# main.net
KiCad netlist of a schematic drawn in EAGLE
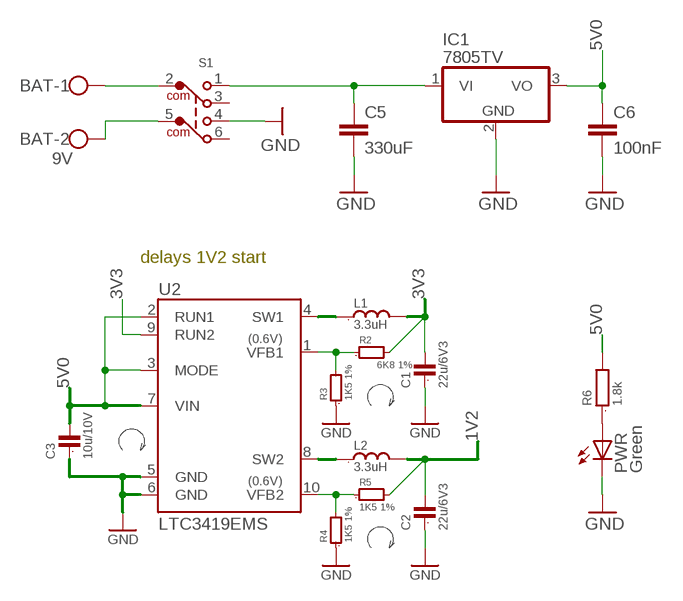
[diagram p0: schematic, sheet 1]
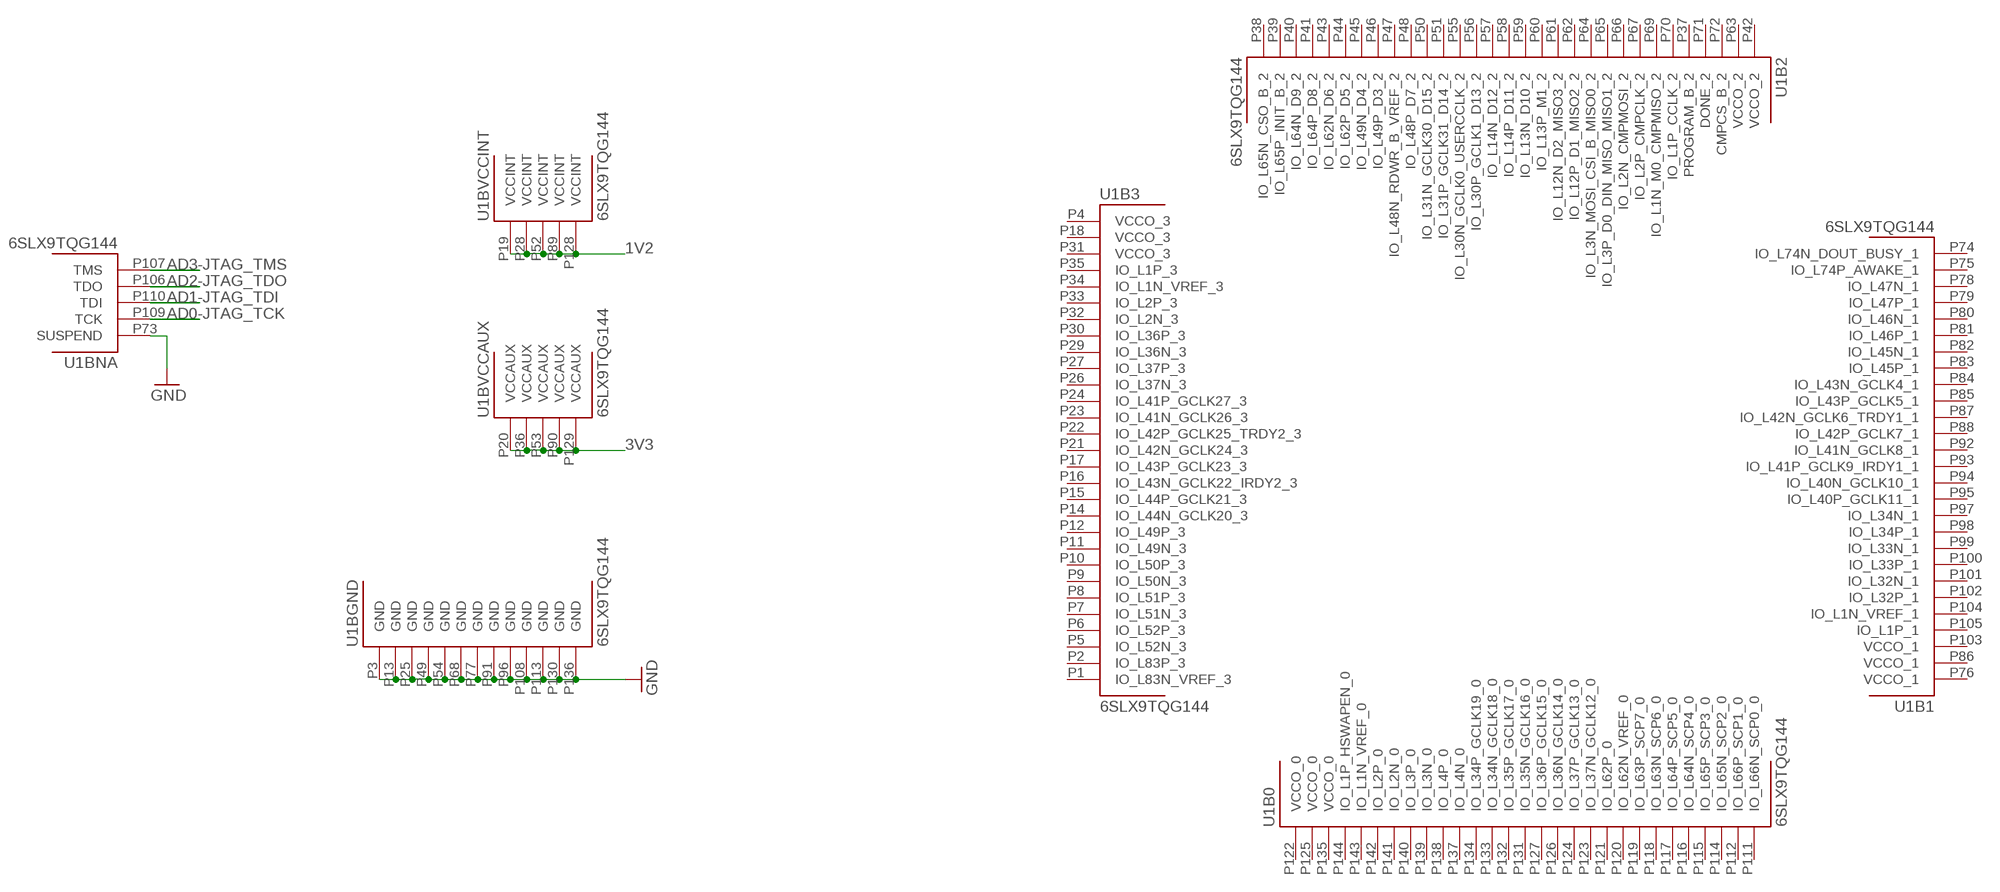
[diagram p1: schematic, sheet 2]

(export (version "E")
  (design (tool "Eeschema 10.0.6"))
  (components
    (comp (ref "BAT")
      (value "9V")
      (footprint "eagle-import:W237-102")
      (fields (field (name "MPN") "237-102"))
      (libsource (lib "eagle-import") (part "W237-102"))
    )
    (comp (ref "C1")
      (value "22u/6V3")
      (footprint "eagle-import:0805")
      (fields (field (name "PARTNO") "GRM21BR60J226ME39L"))
      (libsource (lib "eagle-import") (part "C0805"))
    )
    (comp (ref "C2")
      (value "22u/6V3")
      (footprint "eagle-import:0805")
      (fields (field (name "PARTNO") "GRM21BR60J226ME39L"))
      (libsource (lib "eagle-import") (part "C0805"))
    )
    (comp (ref "C3")
      (value "10u/10V")
      (footprint "eagle-import:0805")
      (fields (field (name "PARTNO") "C0805C106K9PACTU"))
      (libsource (lib "eagle-import") (part "C0805"))
    )
    (comp (ref "C5")
      (value "330uF")
      (footprint "eagle-import:C0805")
      (libsource (lib "eagle-import") (part "C-EUC0805"))
    )
    (comp (ref "C6")
      (value "100nF")
      (footprint "eagle-import:C0805")
      (libsource (lib "eagle-import") (part "C-EUC0805"))
    )
    (comp (ref "IC1")
      (value "7805TV")
      (footprint "eagle-import:TO220V")
      (libsource (lib "eagle-import") (part "78TV05"))
    )
    (comp (ref "L1")
      (value "3.3uH")
      (footprint "eagle-import:VLS3015")
      (fields (field (name "PARTNO") "VLS3015T-3R3M1R2"))
      (libsource (lib "eagle-import") (part "L_VLS3015"))
    )
    (comp (ref "L2")
      (value "3.3uH")
      (footprint "eagle-import:VLS3015")
      (fields (field (name "PARTNO") "VLS3015T-3R3M1R2"))
      (libsource (lib "eagle-import") (part "L_VLS3015"))
    )
    (comp (ref "PWR")
      (value "Green")
      (footprint "eagle-import:CHIP-LED0805")
      (fields (field (name "PARTNO") "LTST-C171EKT"))
      (libsource (lib "eagle-import") (part "LEDCHIP-LED0805"))
    )
    (comp (ref "R2")
      (value "6K8 1%")
      (footprint "eagle-import:0603")
      (fields (field (name "PARTNO") "CRCW06036K80FKEA"))
      (libsource (lib "eagle-import") (part "R-SMALL0603"))
    )
    (comp (ref "R3")
      (value "1K5 1%")
      (footprint "eagle-import:0603")
      (fields (field (name "PARTNO") "CRCW06031K50FKEA"))
      (libsource (lib "eagle-import") (part "R-SMALL0603"))
    )
    (comp (ref "R4")
      (value "1K5 1%")
      (footprint "eagle-import:0603")
      (fields (field (name "PARTNO") "CRCW06031K50FKEA"))
      (libsource (lib "eagle-import") (part "R-SMALL0603"))
    )
    (comp (ref "R5")
      (value "1K5 1%")
      (footprint "eagle-import:0603")
      (fields (field (name "PARTNO") "CRCW06031K50FKEA"))
      (libsource (lib "eagle-import") (part "R-SMALL0603"))
    )
    (comp (ref "R6")
      (value "1.8k")
      (footprint "eagle-import:0603")
      (fields (field (name "PARTNO") "RMCF0603JT1K80"))
      (libsource (lib "eagle-import") (part "R0603"))
    )
    (comp (ref "S1")
      (value "452404020202")
      (footprint "eagle-import:452404020202")
      (libsource (lib "eagle-import") (part "452404020202"))
    )
    (comp (ref "U2")
      (value "LTC3419EMS")
      (footprint "eagle-import:MSOP10")
      (fields (field (name "PARTNO") "LTC3419EMS#PBF"))
      (libsource (lib "eagle-import") (part "LTC3419MSE"))
    )
    (comp (ref "U1")
      (value "6SLX9TQG144")
      (footprint "eagle-import:TQ144")
      (libsource (lib "eagle-import") (part "6SLX9TQG144"))
    )
  )
  (nets
    (net (code "1") (name "1V2") (class "Default")
      (node (ref "C2") (pin "2") (pinfunction "2_2") (pintype "passive"))
      (node (ref "L2") (pin "2") (pinfunction "2_2") (pintype "passive"))
      (node (ref "R5") (pin "2") (pinfunction "2_2") (pintype "passive"))
      (node (ref "U1") (pin "P128") (pinfunction "VCCINT_P128") (pintype "input"))
      (node (ref "U1") (pin "P19") (pinfunction "VCCINT_P19") (pintype "input"))
      (node (ref "U1") (pin "P28") (pinfunction "VCCINT_P28") (pintype "input"))
      (node (ref "U1") (pin "P52") (pinfunction "VCCINT_P52") (pintype "input"))
      (node (ref "U1") (pin "P89") (pinfunction "VCCINT_P89") (pintype "input"))
    )
    (net (code "2") (name "3V3") (class "Default")
      (node (ref "C1") (pin "2") (pinfunction "2_2") (pintype "passive"))
      (node (ref "L1") (pin "2") (pinfunction "2_2") (pintype "passive"))
      (node (ref "R2") (pin "2") (pinfunction "2_2") (pintype "passive"))
      (node (ref "U1") (pin "P129") (pinfunction "VCCAUX_P129") (pintype "input"))
      (node (ref "U1") (pin "P20") (pinfunction "VCCAUX_P20") (pintype "input"))
      (node (ref "U1") (pin "P36") (pinfunction "VCCAUX_P36") (pintype "input"))
      (node (ref "U1") (pin "P53") (pinfunction "VCCAUX_P53") (pintype "input"))
      (node (ref "U1") (pin "P90") (pinfunction "VCCAUX_P90") (pintype "input"))
      (node (ref "U2") (pin "9") (pinfunction "RUN2_9") (pintype "input"))
    )
    (net (code "3") (name "5V0") (class "Default")
      (node (ref "C3") (pin "2") (pinfunction "2_2") (pintype "passive"))
      (node (ref "C6") (pin "1") (pinfunction "1_1") (pintype "passive"))
      (node (ref "IC1") (pin "3") (pinfunction "VO_3") (pintype "passive"))
      (node (ref "R6") (pin "2") (pinfunction "2_2") (pintype "passive"))
      (node (ref "U2") (pin "2") (pinfunction "RUN1_2") (pintype "input"))
      (node (ref "U2") (pin "3") (pinfunction "MODE_3") (pintype "input"))
      (node (ref "U2") (pin "7") (pinfunction "VIN_7") (pintype "input"))
    )
    (net (code "4") (name "AD0-JTAG_TCK") (class "Default")
      (node (ref "U1") (pin "P109") (pinfunction "TCK_P109") (pintype "input"))
    )
    (net (code "5") (name "AD1-JTAG_TDI") (class "Default")
      (node (ref "U1") (pin "P110") (pinfunction "TDI_P110") (pintype "input"))
    )
    (net (code "6") (name "AD2-JTAG_TDO") (class "Default")
      (node (ref "U1") (pin "P106") (pinfunction "TDO_P106") (pintype "output"))
    )
    (net (code "7") (name "AD3-JTAG_TMS") (class "Default")
      (node (ref "U1") (pin "P107") (pinfunction "TMS_P107") (pintype "input"))
    )
    (net (code "8") (name "GND") (class "Default")
      (node (ref "C1") (pin "1") (pinfunction "1_1") (pintype "passive"))
      (node (ref "C2") (pin "1") (pinfunction "1_1") (pintype "passive"))
      (node (ref "C3") (pin "1") (pinfunction "1_1") (pintype "passive"))
      (node (ref "C5") (pin "2") (pinfunction "2_2") (pintype "passive"))
      (node (ref "C6") (pin "2") (pinfunction "2_2") (pintype "passive"))
      (node (ref "IC1") (pin "2") (pinfunction "GND_2") (pintype "passive"))
      (node (ref "PWR") (pin "C") (pinfunction "C_C") (pintype "passive"))
      (node (ref "R3") (pin "1") (pinfunction "1_1") (pintype "passive"))
      (node (ref "R4") (pin "1") (pinfunction "1_1") (pintype "passive"))
      (node (ref "S1") (pin "4") (pinfunction "4_4") (pintype "passive"))
      (node (ref "U1") (pin "P108") (pinfunction "GND_P108") (pintype "power_in"))
      (node (ref "U1") (pin "P113") (pinfunction "GND_P113") (pintype "power_in"))
      (node (ref "U1") (pin "P13") (pinfunction "GND_P13") (pintype "power_in"))
      (node (ref "U1") (pin "P130") (pinfunction "GND_P130") (pintype "power_in"))
      (node (ref "U1") (pin "P136") (pinfunction "GND_P136") (pintype "power_in"))
      (node (ref "U1") (pin "P25") (pinfunction "GND_P25") (pintype "power_in"))
      (node (ref "U1") (pin "P3") (pinfunction "GND_P3") (pintype "power_in"))
      (node (ref "U1") (pin "P49") (pinfunction "GND_P49") (pintype "power_in"))
      (node (ref "U1") (pin "P54") (pinfunction "GND_P54") (pintype "power_in"))
      (node (ref "U1") (pin "P68") (pinfunction "GND_P68") (pintype "power_in"))
      (node (ref "U1") (pin "P73") (pinfunction "SUSPEND_P73") (pintype "input"))
      (node (ref "U1") (pin "P77") (pinfunction "GND_P77") (pintype "power_in"))
      (node (ref "U1") (pin "P91") (pinfunction "GND_P91") (pintype "power_in"))
      (node (ref "U1") (pin "P96") (pinfunction "GND_P96") (pintype "power_in"))
      (node (ref "U2") (pin "5") (pinfunction "GND_5") (pintype "power_in"))
      (node (ref "U2") (pin "6") (pinfunction "GND_6") (pintype "power_in"))
    )
    (net (code "9") (name "Net-(BATA-KL)") (class "Default")
      (node (ref "BAT") (pin "1") (pinfunction "KL_1") (pintype "passive"))
      (node (ref "S1") (pin "2") (pinfunction "COM_2") (pintype "passive"))
    )
    (net (code "10") (name "Net-(BATB-KL)") (class "Default")
      (node (ref "BAT") (pin "2") (pinfunction "KL_2") (pintype "passive"))
      (node (ref "S1") (pin "5") (pinfunction "COM1_5") (pintype "passive"))
    )
    (net (code "11") (name "Net-(IC1-VI)") (class "Default")
      (node (ref "C5") (pin "1") (pinfunction "1_1") (pintype "passive"))
      (node (ref "IC1") (pin "1") (pinfunction "VI_1") (pintype "input"))
      (node (ref "S1") (pin "1") (pinfunction "1_1") (pintype "passive"))
    )
    (net (code "12") (name "Net-(PWR-PadA)") (class "Default")
      (node (ref "PWR") (pin "A") (pinfunction "A_A") (pintype "passive"))
      (node (ref "R6") (pin "1") (pinfunction "1_1") (pintype "passive"))
    )
    (net (code "13") (name "Net-(U2-SW1)") (class "Default")
      (node (ref "L1") (pin "1") (pinfunction "1_1") (pintype "passive"))
      (node (ref "U2") (pin "4") (pinfunction "SW1_4") (pintype "output"))
    )
    (net (code "14") (name "Net-(U2-SW2)") (class "Default")
      (node (ref "L2") (pin "1") (pinfunction "1_1") (pintype "passive"))
      (node (ref "U2") (pin "8") (pinfunction "SW2_8") (pintype "output"))
    )
    (net (code "15") (name "Net-(U2-VFB1)") (class "Default")
      (node (ref "R2") (pin "1") (pinfunction "1_1") (pintype "passive"))
      (node (ref "R3") (pin "2") (pinfunction "2_2") (pintype "passive"))
      (node (ref "U2") (pin "1") (pinfunction "VFB1_1") (pintype "input"))
    )
    (net (code "16") (name "Net-(U2-VFB2)") (class "Default")
      (node (ref "R4") (pin "2") (pinfunction "2_2") (pintype "passive"))
      (node (ref "R5") (pin "1") (pinfunction "1_1") (pintype "passive"))
      (node (ref "U2") (pin "10") (pinfunction "VFB2_10") (pintype "input"))
    )
    (net (code "17") (name "unconnected-(S1-Pad3)") (class "Default")
      (node (ref "S1") (pin "3") (pinfunction "3_3") (pintype "passive"))
    )
    (net (code "18") (name "unconnected-(S1-Pad6)") (class "Default")
      (node (ref "S1") (pin "6") (pinfunction "6_6") (pintype "passive"))
    )
    (net (code "19") (name "unconnected-(U1A-IO_L1N_VREF_0-PadP143)") (class "Default")
      (node (ref "U1") (pin "P143") (pinfunction "IO_L1N_VREF_0_P143") (pintype "bidirectional"))
    )
    (net (code "20") (name "unconnected-(U1A-IO_L1P_HSWAPEN_0-PadP144)") (class "Default")
      (node (ref "U1") (pin "P144") (pinfunction "IO_L1P_HSWAPEN_0_P144") (pintype "bidirectional"))
    )
    (net (code "21") (name "unconnected-(U1A-IO_L2N_0-PadP141)") (class "Default")
      (node (ref "U1") (pin "P141") (pinfunction "IO_L2N_0_P141") (pintype "bidirectional"))
    )
    (net (code "22") (name "unconnected-(U1A-IO_L2P_0-PadP142)") (class "Default")
      (node (ref "U1") (pin "P142") (pinfunction "IO_L2P_0_P142") (pintype "bidirectional"))
    )
    (net (code "23") (name "unconnected-(U1A-IO_L3N_0-PadP139)") (class "Default")
      (node (ref "U1") (pin "P139") (pinfunction "IO_L3N_0_P139") (pintype "bidirectional"))
    )
    (net (code "24") (name "unconnected-(U1A-IO_L3P_0-PadP140)") (class "Default")
      (node (ref "U1") (pin "P140") (pinfunction "IO_L3P_0_P140") (pintype "bidirectional"))
    )
    (net (code "25") (name "unconnected-(U1A-IO_L4N_0-PadP137)") (class "Default")
      (node (ref "U1") (pin "P137") (pinfunction "IO_L4N_0_P137") (pintype "bidirectional"))
    )
    (net (code "26") (name "unconnected-(U1A-IO_L4P_0-PadP138)") (class "Default")
      (node (ref "U1") (pin "P138") (pinfunction "IO_L4P_0_P138") (pintype "bidirectional"))
    )
    (net (code "27") (name "unconnected-(U1A-IO_L34N_GCLK18_0-PadP133)") (class "Default")
      (node (ref "U1") (pin "P133") (pinfunction "IO_L34N_GCLK18_0_P133") (pintype "bidirectional"))
    )
    (net (code "28") (name "unconnected-(U1A-IO_L34P_GCLK19_0-PadP134)") (class "Default")
      (node (ref "U1") (pin "P134") (pinfunction "IO_L34P_GCLK19_0_P134") (pintype "bidirectional"))
    )
    (net (code "29") (name "unconnected-(U1A-IO_L35N_GCLK16_0-PadP131)") (class "Default")
      (node (ref "U1") (pin "P131") (pinfunction "IO_L35N_GCLK16_0_P131") (pintype "bidirectional"))
    )
    (net (code "30") (name "unconnected-(U1A-IO_L35P_GCLK17_0-PadP132)") (class "Default")
      (node (ref "U1") (pin "P132") (pinfunction "IO_L35P_GCLK17_0_P132") (pintype "bidirectional"))
    )
    (net (code "31") (name "unconnected-(U1A-IO_L36N_GCLK14_0-PadP126)") (class "Default")
      (node (ref "U1") (pin "P126") (pinfunction "IO_L36N_GCLK14_0_P126") (pintype "bidirectional"))
    )
    (net (code "32") (name "unconnected-(U1A-IO_L36P_GCLK15_0-PadP127)") (class "Default")
      (node (ref "U1") (pin "P127") (pinfunction "IO_L36P_GCLK15_0_P127") (pintype "bidirectional"))
    )
    (net (code "33") (name "unconnected-(U1A-IO_L37N_GCLK12_0-PadP123)") (class "Default")
      (node (ref "U1") (pin "P123") (pinfunction "IO_L37N_GCLK12_0_P123") (pintype "bidirectional"))
    )
    (net (code "34") (name "unconnected-(U1A-IO_L37P_GCLK13_0-PadP124)") (class "Default")
      (node (ref "U1") (pin "P124") (pinfunction "IO_L37P_GCLK13_0_P124") (pintype "bidirectional"))
    )
    (net (code "35") (name "unconnected-(U1A-IO_L62N_VREF_0-PadP120)") (class "Default")
      (node (ref "U1") (pin "P120") (pinfunction "IO_L62N_VREF_0_P120") (pintype "bidirectional"))
    )
    (net (code "36") (name "unconnected-(U1A-IO_L62P_0-PadP121)") (class "Default")
      (node (ref "U1") (pin "P121") (pinfunction "IO_L62P_0_P121") (pintype "bidirectional"))
    )
    (net (code "37") (name "unconnected-(U1A-IO_L63N_SCP6_0-PadP118)") (class "Default")
      (node (ref "U1") (pin "P118") (pinfunction "IO_L63N_SCP6_0_P118") (pintype "bidirectional"))
    )
    (net (code "38") (name "unconnected-(U1A-IO_L63P_SCP7_0-PadP119)") (class "Default")
      (node (ref "U1") (pin "P119") (pinfunction "IO_L63P_SCP7_0_P119") (pintype "bidirectional"))
    )
    (net (code "39") (name "unconnected-(U1A-IO_L64N_SCP4_0-PadP116)") (class "Default")
      (node (ref "U1") (pin "P116") (pinfunction "IO_L64N_SCP4_0_P116") (pintype "bidirectional"))
    )
    (net (code "40") (name "unconnected-(U1A-IO_L64P_SCP5_0-PadP117)") (class "Default")
      (node (ref "U1") (pin "P117") (pinfunction "IO_L64P_SCP5_0_P117") (pintype "bidirectional"))
    )
    (net (code "41") (name "unconnected-(U1A-IO_L65N_SCP2_0-PadP114)") (class "Default")
      (node (ref "U1") (pin "P114") (pinfunction "IO_L65N_SCP2_0_P114") (pintype "bidirectional"))
    )
    (net (code "42") (name "unconnected-(U1A-IO_L65P_SCP3_0-PadP115)") (class "Default")
      (node (ref "U1") (pin "P115") (pinfunction "IO_L65P_SCP3_0_P115") (pintype "bidirectional"))
    )
    (net (code "43") (name "unconnected-(U1A-IO_L66N_SCP0_0-PadP111)") (class "Default")
      (node (ref "U1") (pin "P111") (pinfunction "IO_L66N_SCP0_0_P111") (pintype "bidirectional"))
    )
    (net (code "44") (name "unconnected-(U1A-IO_L66P_SCP1_0-PadP112)") (class "Default")
      (node (ref "U1") (pin "P112") (pinfunction "IO_L66P_SCP1_0_P112") (pintype "bidirectional"))
    )
    (net (code "45") (name "unconnected-(U1A-VCCO_0-PadP122)") (class "Default")
      (node (ref "U1") (pin "P122") (pinfunction "VCCO_0_P122") (pintype "input"))
    )
    (net (code "46") (name "unconnected-(U1A-VCCO_0-PadP125)") (class "Default")
      (node (ref "U1") (pin "P125") (pinfunction "VCCO_0_P125") (pintype "input"))
    )
    (net (code "47") (name "unconnected-(U1A-VCCO_0-PadP135)") (class "Default")
      (node (ref "U1") (pin "P135") (pinfunction "VCCO_0_P135") (pintype "input"))
    )
    (net (code "48") (name "unconnected-(U1B-IO_L1N_VREF_1-PadP104)") (class "Default")
      (node (ref "U1") (pin "P104") (pinfunction "IO_L1N_VREF_1_P104") (pintype "bidirectional"))
    )
    (net (code "49") (name "unconnected-(U1B-IO_L1P_1-PadP105)") (class "Default")
      (node (ref "U1") (pin "P105") (pinfunction "IO_L1P_1_P105") (pintype "bidirectional"))
    )
    (net (code "50") (name "unconnected-(U1B-IO_L32N_1-PadP101)") (class "Default")
      (node (ref "U1") (pin "P101") (pinfunction "IO_L32N_1_P101") (pintype "bidirectional"))
    )
    (net (code "51") (name "unconnected-(U1B-IO_L32P_1-PadP102)") (class "Default")
      (node (ref "U1") (pin "P102") (pinfunction "IO_L32P_1_P102") (pintype "bidirectional"))
    )
    (net (code "52") (name "unconnected-(U1B-IO_L33N_1-PadP99)") (class "Default")
      (node (ref "U1") (pin "P99") (pinfunction "IO_L33N_1_P99") (pintype "bidirectional"))
    )
    (net (code "53") (name "unconnected-(U1B-IO_L33P_1-PadP100)") (class "Default")
      (node (ref "U1") (pin "P100") (pinfunction "IO_L33P_1_P100") (pintype "bidirectional"))
    )
    (net (code "54") (name "unconnected-(U1B-IO_L34N_1-PadP97)") (class "Default")
      (node (ref "U1") (pin "P97") (pinfunction "IO_L34N_1_P97") (pintype "bidirectional"))
    )
    (net (code "55") (name "unconnected-(U1B-IO_L34P_1-PadP98)") (class "Default")
      (node (ref "U1") (pin "P98") (pinfunction "IO_L34P_1_P98") (pintype "bidirectional"))
    )
    (net (code "56") (name "unconnected-(U1B-IO_L40N_GCLK10_1-PadP94)") (class "Default")
      (node (ref "U1") (pin "P94") (pinfunction "IO_L40N_GCLK10_1_P94") (pintype "bidirectional"))
    )
    (net (code "57") (name "unconnected-(U1B-IO_L40P_GCLK11_1-PadP95)") (class "Default")
      (node (ref "U1") (pin "P95") (pinfunction "IO_L40P_GCLK11_1_P95") (pintype "bidirectional"))
    )
    (net (code "58") (name "unconnected-(U1B-IO_L41N_GCLK8_1-PadP92)") (class "Default")
      (node (ref "U1") (pin "P92") (pinfunction "IO_L41N_GCLK8_1_P92") (pintype "bidirectional"))
    )
    (net (code "59") (name "unconnected-(U1B-IO_L41P_GCLK9_IRDY1_1-PadP93)") (class "Default")
      (node (ref "U1") (pin "P93") (pinfunction "IO_L41P_GCLK9_IRDY1_1_P93") (pintype "bidirectional"))
    )
    (net (code "60") (name "unconnected-(U1B-IO_L42N_GCLK6_TRDY1_1-PadP87)") (class "Default")
      (node (ref "U1") (pin "P87") (pinfunction "IO_L42N_GCLK6_TRDY1_1_P87") (pintype "bidirectional"))
    )
    (net (code "61") (name "unconnected-(U1B-IO_L42P_GCLK7_1-PadP88)") (class "Default")
      (node (ref "U1") (pin "P88") (pinfunction "IO_L42P_GCLK7_1_P88") (pintype "bidirectional"))
    )
    (net (code "62") (name "unconnected-(U1B-IO_L43N_GCLK4_1-PadP84)") (class "Default")
      (node (ref "U1") (pin "P84") (pinfunction "IO_L43N_GCLK4_1_P84") (pintype "bidirectional"))
    )
    (net (code "63") (name "unconnected-(U1B-IO_L43P_GCLK5_1-PadP85)") (class "Default")
      (node (ref "U1") (pin "P85") (pinfunction "IO_L43P_GCLK5_1_P85") (pintype "bidirectional"))
    )
    (net (code "64") (name "unconnected-(U1B-IO_L45N_1-PadP82)") (class "Default")
      (node (ref "U1") (pin "P82") (pinfunction "IO_L45N_1_P82") (pintype "bidirectional"))
    )
    (net (code "65") (name "unconnected-(U1B-IO_L45P_1-PadP83)") (class "Default")
      (node (ref "U1") (pin "P83") (pinfunction "IO_L45P_1_P83") (pintype "bidirectional"))
    )
    (net (code "66") (name "unconnected-(U1B-IO_L46N_1-PadP80)") (class "Default")
      (node (ref "U1") (pin "P80") (pinfunction "IO_L46N_1_P80") (pintype "bidirectional"))
    )
    (net (code "67") (name "unconnected-(U1B-IO_L46P_1-PadP81)") (class "Default")
      (node (ref "U1") (pin "P81") (pinfunction "IO_L46P_1_P81") (pintype "bidirectional"))
    )
    (net (code "68") (name "unconnected-(U1B-IO_L47N_1-PadP78)") (class "Default")
      (node (ref "U1") (pin "P78") (pinfunction "IO_L47N_1_P78") (pintype "bidirectional"))
    )
    (net (code "69") (name "unconnected-(U1B-IO_L47P_1-PadP79)") (class "Default")
      (node (ref "U1") (pin "P79") (pinfunction "IO_L47P_1_P79") (pintype "bidirectional"))
    )
    (net (code "70") (name "unconnected-(U1B-IO_L74N_DOUT_BUSY_1-PadP74)") (class "Default")
      (node (ref "U1") (pin "P74") (pinfunction "IO_L74N_DOUT_BUSY_1_P74") (pintype "bidirectional"))
    )
    (net (code "71") (name "unconnected-(U1B-IO_L74P_AWAKE_1-PadP75)") (class "Default")
      (node (ref "U1") (pin "P75") (pinfunction "IO_L74P_AWAKE_1_P75") (pintype "bidirectional"))
    )
    (net (code "72") (name "unconnected-(U1B-VCCO_1-PadP76)") (class "Default")
      (node (ref "U1") (pin "P76") (pinfunction "VCCO_1_P76") (pintype "input"))
    )
    (net (code "73") (name "unconnected-(U1B-VCCO_1-PadP86)") (class "Default")
      (node (ref "U1") (pin "P86") (pinfunction "VCCO_1_P86") (pintype "input"))
    )
    (net (code "74") (name "unconnected-(U1B-VCCO_1-PadP103)") (class "Default")
      (node (ref "U1") (pin "P103") (pinfunction "VCCO_1_P103") (pintype "input"))
    )
    (net (code "75") (name "unconnected-(U1C-CMPCS_B_2-PadP72)") (class "Default")
      (node (ref "U1") (pin "P72") (pinfunction "CMPCS_B_2_P72") (pintype "bidirectional"))
    )
    (net (code "76") (name "unconnected-(U1C-DONE_2-PadP71)") (class "Default")
      (node (ref "U1") (pin "P71") (pinfunction "DONE_2_P71") (pintype "bidirectional"))
    )
    (net (code "77") (name "unconnected-(U1C-IO_L1N_M0_CMPMISO_2-PadP69)") (class "Default")
      (node (ref "U1") (pin "P69") (pinfunction "IO_L1N_M0_CMPMISO_2_P69") (pintype "bidirectional"))
    )
    (net (code "78") (name "unconnected-(U1C-IO_L1P_CCLK_2-PadP70)") (class "Default")
      (node (ref "U1") (pin "P70") (pinfunction "IO_L1P_CCLK_2_P70") (pintype "bidirectional"))
    )
    (net (code "79") (name "unconnected-(U1C-IO_L2N_CMPMOSI_2-PadP66)") (class "Default")
      (node (ref "U1") (pin "P66") (pinfunction "IO_L2N_CMPMOSI_2_P66") (pintype "bidirectional"))
    )
    (net (code "80") (name "unconnected-(U1C-IO_L2P_CMPCLK_2-PadP67)") (class "Default")
      (node (ref "U1") (pin "P67") (pinfunction "IO_L2P_CMPCLK_2_P67") (pintype "bidirectional"))
    )
    (net (code "81") (name "unconnected-(U1C-IO_L3N_MOSI_CSI_B_MISO0_2-PadP64)") (class "Default")
      (node (ref "U1") (pin "P64") (pinfunction "IO_L3N_MOSI_CSI_B_MISO0_2_P64") (pintype "bidirectional"))
    )
    (net (code "82") (name "unconnected-(U1C-IO_L3P_D0_DIN_MISO_MISO1_2-PadP65)") (class "Default")
      (node (ref "U1") (pin "P65") (pinfunction "IO_L3P_D0_DIN_MISO_MISO1_2_P65") (pintype "bidirectional"))
    )
    (net (code "83") (name "unconnected-(U1C-IO_L12N_D2_MISO3_2-PadP61)") (class "Default")
      (node (ref "U1") (pin "P61") (pinfunction "IO_L12N_D2_MISO3_2_P61") (pintype "bidirectional"))
    )
    (net (code "84") (name "unconnected-(U1C-IO_L12P_D1_MISO2_2-PadP62)") (class "Default")
      (node (ref "U1") (pin "P62") (pinfunction "IO_L12P_D1_MISO2_2_P62") (pintype "bidirectional"))
    )
    (net (code "85") (name "unconnected-(U1C-IO_L13N_D10_2-PadP59)") (class "Default")
      (node (ref "U1") (pin "P59") (pinfunction "IO_L13N_D10_2_P59") (pintype "bidirectional"))
    )
    (net (code "86") (name "unconnected-(U1C-IO_L13P_M1_2-PadP60)") (class "Default")
      (node (ref "U1") (pin "P60") (pinfunction "IO_L13P_M1_2_P60") (pintype "bidirectional"))
    )
    (net (code "87") (name "unconnected-(U1C-IO_L14N_D12_2-PadP57)") (class "Default")
      (node (ref "U1") (pin "P57") (pinfunction "IO_L14N_D12_2_P57") (pintype "bidirectional"))
    )
    (net (code "88") (name "unconnected-(U1C-IO_L14P_D11_2-PadP58)") (class "Default")
      (node (ref "U1") (pin "P58") (pinfunction "IO_L14P_D11_2_P58") (pintype "bidirectional"))
    )
    (net (code "89") (name "unconnected-(U1C-IO_L30N_GCLK0_USERCCLK_2-PadP55)") (class "Default")
      (node (ref "U1") (pin "P55") (pinfunction "IO_L30N_GCLK0_USERCCLK_2_P55") (pintype "bidirectional"))
    )
    (net (code "90") (name "unconnected-(U1C-IO_L30P_GCLK1_D13_2-PadP56)") (class "Default")
      (node (ref "U1") (pin "P56") (pinfunction "IO_L30P_GCLK1_D13_2_P56") (pintype "bidirectional"))
    )
    (net (code "91") (name "unconnected-(U1C-IO_L31N_GCLK30_D15_2-PadP50)") (class "Default")
      (node (ref "U1") (pin "P50") (pinfunction "IO_L31N_GCLK30_D15_2_P50") (pintype "bidirectional"))
    )
    (net (code "92") (name "unconnected-(U1C-IO_L31P_GCLK31_D14_2-PadP51)") (class "Default")
      (node (ref "U1") (pin "P51") (pinfunction "IO_L31P_GCLK31_D14_2_P51") (pintype "bidirectional"))
    )
    (net (code "93") (name "unconnected-(U1C-IO_L48N_RDWR_B_VREF_2-PadP47)") (class "Default")
      (node (ref "U1") (pin "P47") (pinfunction "IO_L48N_RDWR_B_VREF_2_P47") (pintype "bidirectional"))
    )
    (net (code "94") (name "unconnected-(U1C-IO_L48P_D7_2-PadP48)") (class "Default")
      (node (ref "U1") (pin "P48") (pinfunction "IO_L48P_D7_2_P48") (pintype "bidirectional"))
    )
    (net (code "95") (name "unconnected-(U1C-IO_L49N_D4_2-PadP45)") (class "Default")
      (node (ref "U1") (pin "P45") (pinfunction "IO_L49N_D4_2_P45") (pintype "bidirectional"))
    )
    (net (code "96") (name "unconnected-(U1C-IO_L49P_D3_2-PadP46)") (class "Default")
      (node (ref "U1") (pin "P46") (pinfunction "IO_L49P_D3_2_P46") (pintype "bidirectional"))
    )
    (net (code "97") (name "unconnected-(U1C-IO_L62N_D6_2-PadP43)") (class "Default")
      (node (ref "U1") (pin "P43") (pinfunction "IO_L62N_D6_2_P43") (pintype "bidirectional"))
    )
    (net (code "98") (name "unconnected-(U1C-IO_L62P_D5_2-PadP44)") (class "Default")
      (node (ref "U1") (pin "P44") (pinfunction "IO_L62P_D5_2_P44") (pintype "bidirectional"))
    )
    (net (code "99") (name "unconnected-(U1C-IO_L64N_D9_2-PadP40)") (class "Default")
      (node (ref "U1") (pin "P40") (pinfunction "IO_L64N_D9_2_P40") (pintype "bidirectional"))
    )
    (net (code "100") (name "unconnected-(U1C-IO_L64P_D8_2-PadP41)") (class "Default")
      (node (ref "U1") (pin "P41") (pinfunction "IO_L64P_D8_2_P41") (pintype "bidirectional"))
    )
    (net (code "101") (name "unconnected-(U1C-IO_L65N_CSO_B_2-PadP38)") (class "Default")
      (node (ref "U1") (pin "P38") (pinfunction "IO_L65N_CSO_B_2_P38") (pintype "bidirectional"))
    )
    (net (code "102") (name "unconnected-(U1C-IO_L65P_INIT_B_2-PadP39)") (class "Default")
      (node (ref "U1") (pin "P39") (pinfunction "IO_L65P_INIT_B_2_P39") (pintype "bidirectional"))
    )
    (net (code "103") (name "unconnected-(U1C-PROGRAM_B_2-PadP37)") (class "Default")
      (node (ref "U1") (pin "P37") (pinfunction "PROGRAM_B_2_P37") (pintype "input"))
    )
    (net (code "104") (name "unconnected-(U1C-VCCO_2-PadP42)") (class "Default")
      (node (ref "U1") (pin "P42") (pinfunction "VCCO_2_P42") (pintype "input"))
    )
    (net (code "105") (name "unconnected-(U1C-VCCO_2-PadP63)") (class "Default")
      (node (ref "U1") (pin "P63") (pinfunction "VCCO_2_P63") (pintype "input"))
    )
    (net (code "106") (name "unconnected-(U1D-IO_L1N_VREF_3-PadP34)") (class "Default")
      (node (ref "U1") (pin "P34") (pinfunction "IO_L1N_VREF_3_P34") (pintype "bidirectional"))
    )
    (net (code "107") (name "unconnected-(U1D-IO_L1P_3-PadP35)") (class "Default")
      (node (ref "U1") (pin "P35") (pinfunction "IO_L1P_3_P35") (pintype "bidirectional"))
    )
    (net (code "108") (name "unconnected-(U1D-IO_L2N_3-PadP32)") (class "Default")
      (node (ref "U1") (pin "P32") (pinfunction "IO_L2N_3_P32") (pintype "bidirectional"))
    )
    (net (code "109") (name "unconnected-(U1D-IO_L2P_3-PadP33)") (class "Default")
      (node (ref "U1") (pin "P33") (pinfunction "IO_L2P_3_P33") (pintype "bidirectional"))
    )
    (net (code "110") (name "unconnected-(U1D-IO_L36N_3-PadP29)") (class "Default")
      (node (ref "U1") (pin "P29") (pinfunction "IO_L36N_3_P29") (pintype "bidirectional"))
    )
    (net (code "111") (name "unconnected-(U1D-IO_L36P_3-PadP30)") (class "Default")
      (node (ref "U1") (pin "P30") (pinfunction "IO_L36P_3_P30") (pintype "bidirectional"))
    )
    (net (code "112") (name "unconnected-(U1D-IO_L37N_3-PadP26)") (class "Default")
      (node (ref "U1") (pin "P26") (pinfunction "IO_L37N_3_P26") (pintype "bidirectional"))
    )
    (net (code "113") (name "unconnected-(U1D-IO_L37P_3-PadP27)") (class "Default")
      (node (ref "U1") (pin "P27") (pinfunction "IO_L37P_3_P27") (pintype "bidirectional"))
    )
    (net (code "114") (name "unconnected-(U1D-IO_L41N_GCLK26_3-PadP23)") (class "Default")
      (node (ref "U1") (pin "P23") (pinfunction "IO_L41N_GCLK26_3_P23") (pintype "bidirectional"))
    )
    (net (code "115") (name "unconnected-(U1D-IO_L41P_GCLK27_3-PadP24)") (class "Default")
      (node (ref "U1") (pin "P24") (pinfunction "IO_L41P_GCLK27_3_P24") (pintype "bidirectional"))
    )
    (net (code "116") (name "unconnected-(U1D-IO_L42N_GCLK24_3-PadP21)") (class "Default")
      (node (ref "U1") (pin "P21") (pinfunction "IO_L42N_GCLK24_3_P21") (pintype "bidirectional"))
    )
    (net (code "117") (name "unconnected-(U1D-IO_L42P_GCLK25_TRDY2_3-PadP22)") (class "Default")
      (node (ref "U1") (pin "P22") (pinfunction "IO_L42P_GCLK25_TRDY2_3_P22") (pintype "bidirectional"))
    )
    (net (code "118") (name "unconnected-(U1D-IO_L43N_GCLK22_IRDY2_3-PadP16)") (class "Default")
      (node (ref "U1") (pin "P16") (pinfunction "IO_L43N_GCLK22_IRDY2_3_P16") (pintype "bidirectional"))
    )
    (net (code "119") (name "unconnected-(U1D-IO_L43P_GCLK23_3-PadP17)") (class "Default")
      (node (ref "U1") (pin "P17") (pinfunction "IO_L43P_GCLK23_3_P17") (pintype "bidirectional"))
    )
    (net (code "120") (name "unconnected-(U1D-IO_L44N_GCLK20_3-PadP14)") (class "Default")
      (node (ref "U1") (pin "P14") (pinfunction "IO_L44N_GCLK20_3_P14") (pintype "bidirectional"))
    )
    (net (code "121") (name "unconnected-(U1D-IO_L44P_GCLK21_3-PadP15)") (class "Default")
      (node (ref "U1") (pin "P15") (pinfunction "IO_L44P_GCLK21_3_P15") (pintype "bidirectional"))
    )
    (net (code "122") (name "unconnected-(U1D-IO_L49N_3-PadP11)") (class "Default")
      (node (ref "U1") (pin "P11") (pinfunction "IO_L49N_3_P11") (pintype "bidirectional"))
    )
    (net (code "123") (name "unconnected-(U1D-IO_L49P_3-PadP12)") (class "Default")
      (node (ref "U1") (pin "P12") (pinfunction "IO_L49P_3_P12") (pintype "bidirectional"))
    )
    (net (code "124") (name "unconnected-(U1D-IO_L50N_3-PadP9)") (class "Default")
      (node (ref "U1") (pin "P9") (pinfunction "IO_L50N_3_P9") (pintype "bidirectional"))
    )
    (net (code "125") (name "unconnected-(U1D-IO_L50P_3-PadP10)") (class "Default")
      (node (ref "U1") (pin "P10") (pinfunction "IO_L50P_3_P10") (pintype "bidirectional"))
    )
    (net (code "126") (name "unconnected-(U1D-IO_L51N_3-PadP7)") (class "Default")
      (node (ref "U1") (pin "P7") (pinfunction "IO_L51N_3_P7") (pintype "bidirectional"))
    )
    (net (code "127") (name "unconnected-(U1D-IO_L51P_3-PadP8)") (class "Default")
      (node (ref "U1") (pin "P8") (pinfunction "IO_L51P_3_P8") (pintype "bidirectional"))
    )
    (net (code "128") (name "unconnected-(U1D-IO_L52N_3-PadP5)") (class "Default")
      (node (ref "U1") (pin "P5") (pinfunction "IO_L52N_3_P5") (pintype "bidirectional"))
    )
    (net (code "129") (name "unconnected-(U1D-IO_L52P_3-PadP6)") (class "Default")
      (node (ref "U1") (pin "P6") (pinfunction "IO_L52P_3_P6") (pintype "bidirectional"))
    )
    (net (code "130") (name "unconnected-(U1D-IO_L83N_VREF_3-PadP1)") (class "Default")
      (node (ref "U1") (pin "P1") (pinfunction "IO_L83N_VREF_3_P1") (pintype "bidirectional"))
    )
    (net (code "131") (name "unconnected-(U1D-IO_L83P_3-PadP2)") (class "Default")
      (node (ref "U1") (pin "P2") (pinfunction "IO_L83P_3_P2") (pintype "bidirectional"))
    )
    (net (code "132") (name "unconnected-(U1D-VCCO_3-PadP4)") (class "Default")
      (node (ref "U1") (pin "P4") (pinfunction "VCCO_3_P4") (pintype "input"))
    )
    (net (code "133") (name "unconnected-(U1D-VCCO_3-PadP18)") (class "Default")
      (node (ref "U1") (pin "P18") (pinfunction "VCCO_3_P18") (pintype "input"))
    )
    (net (code "134") (name "unconnected-(U1D-VCCO_3-PadP31)") (class "Default")
      (node (ref "U1") (pin "P31") (pinfunction "VCCO_3_P31") (pintype "input"))
    )
  )
)
